# dualHbridge-v5.net
KiCad netlist of a schematic drawn in EAGLE
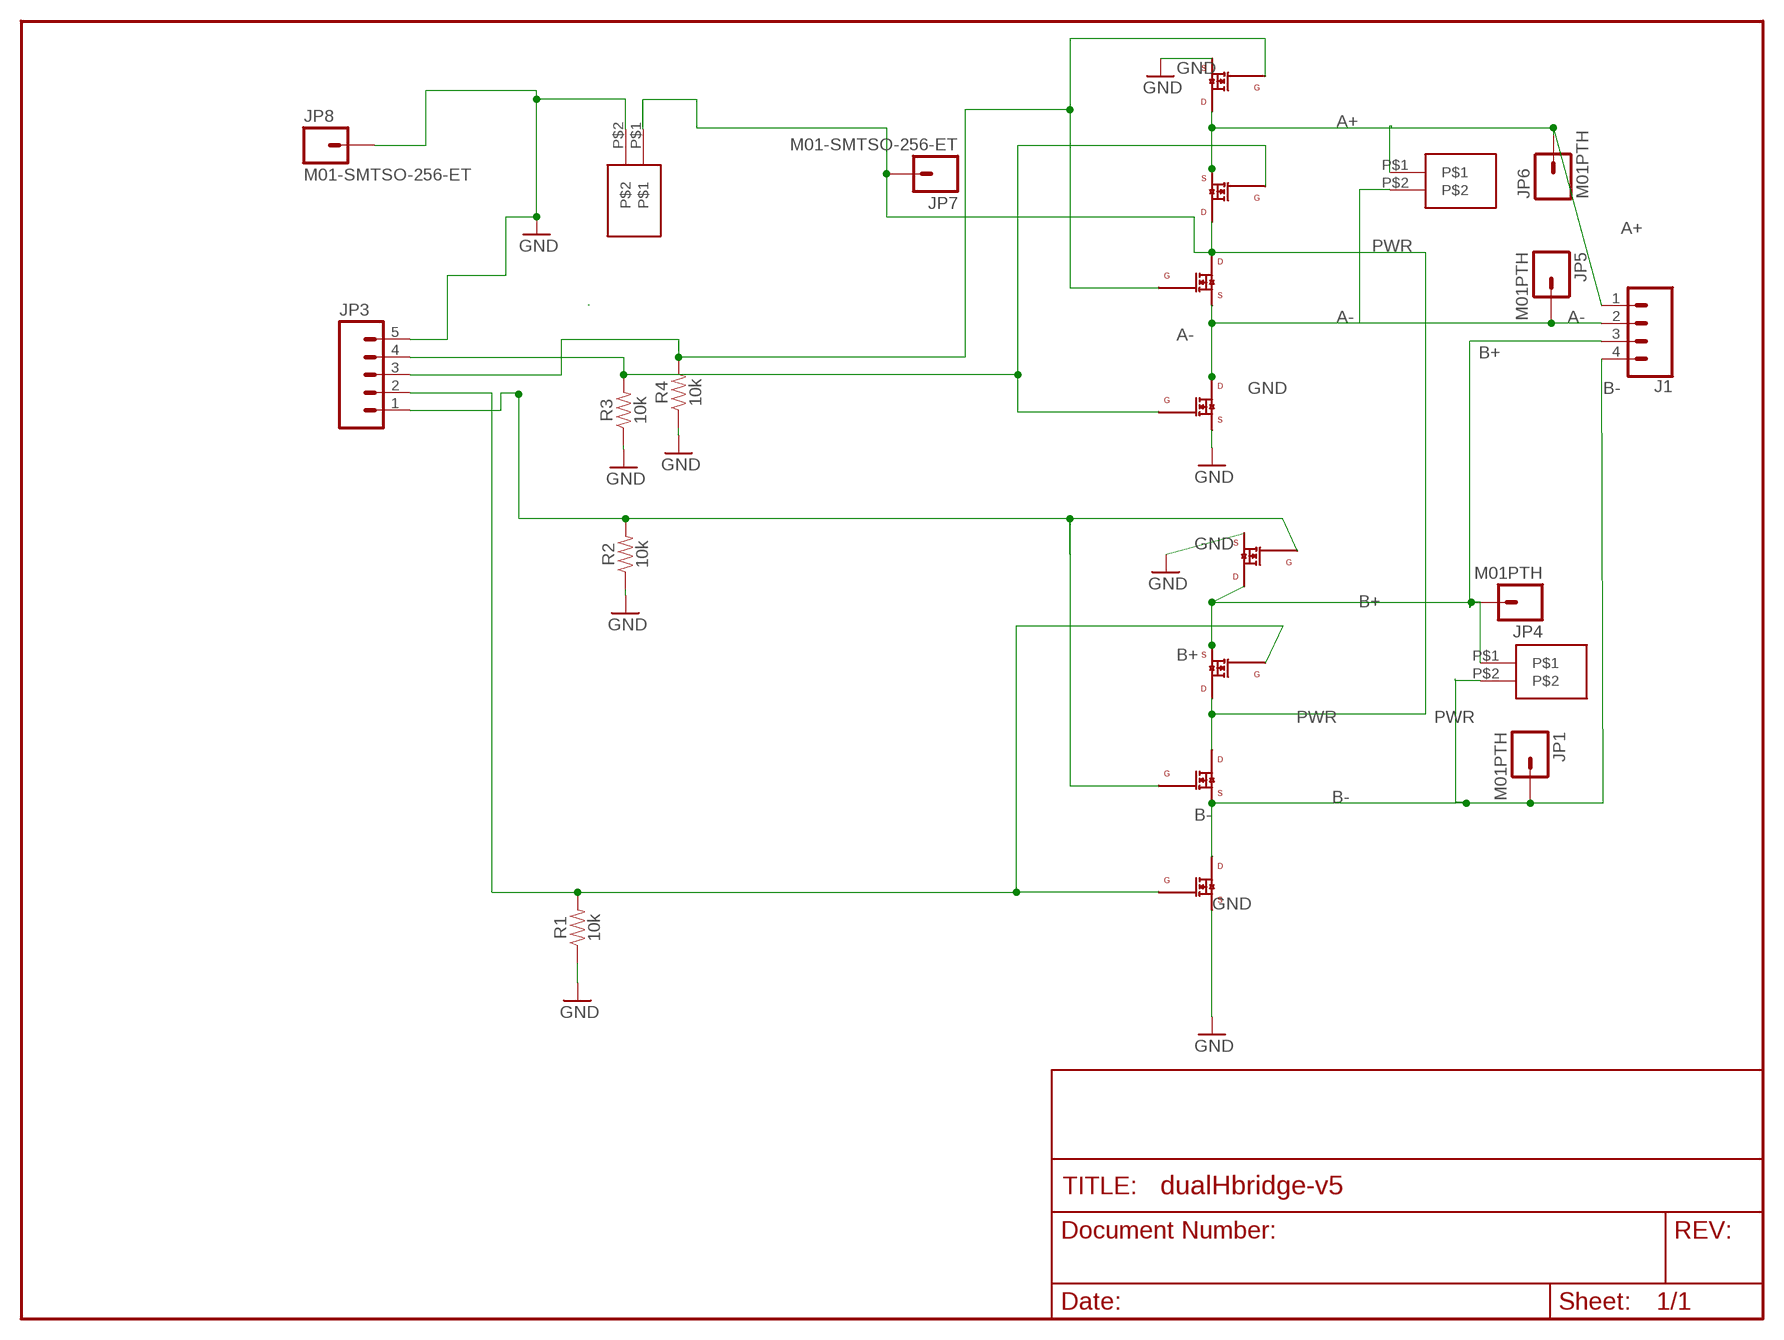
[diagram p0: schematic, sheet 1]

(export (version "E")
  (design (tool "Eeschema 10.0.6"))
  (components
    (comp (ref "J1")
      (value "CONN_04")
      (footprint "eagle-import:1X04")
      (libsource (lib "eagle-import") (part "CONN_04"))
    )
    (comp (ref "JP1")
      (value "M01PTH")
      (footprint "eagle-import:1X01@1")
      (libsource (lib "eagle-import") (part "M01PTH"))
    )
    (comp (ref "JP3")
      (value "M05PTH")
      (footprint "eagle-import:1X05")
      (libsource (lib "eagle-import") (part "M05PTH"))
    )
    (comp (ref "JP4")
      (value "M01PTH")
      (footprint "eagle-import:1X01@1")
      (libsource (lib "eagle-import") (part "M01PTH"))
    )
    (comp (ref "JP5")
      (value "M01PTH")
      (footprint "eagle-import:1X01@1")
      (libsource (lib "eagle-import") (part "M01PTH"))
    )
    (comp (ref "JP6")
      (value "M01PTH")
      (footprint "eagle-import:1X01@1")
      (libsource (lib "eagle-import") (part "M01PTH"))
    )
    (comp (ref "JP7")
      (value "M01-SMTSO-256-ET")
      (footprint "eagle-import:SMTSO-256-ET")
      (libsource (lib "eagle-import") (part "M01-SMTSO-256-ET"))
    )
    (comp (ref "JP8")
      (value "M01-SMTSO-256-ET")
      (footprint "eagle-import:SMTSO-256-ET")
      (libsource (lib "eagle-import") (part "M01-SMTSO-256-ET"))
    )
    (comp (ref "Q1")
      (value "IRLML0060")
      (footprint "eagle-import:SOT-23")
      (libsource (lib "eagle-import") (part "IRLML0060"))
    )
    (comp (ref "Q2")
      (value "IRLML0060")
      (footprint "eagle-import:SOT-23")
      (libsource (lib "eagle-import") (part "IRLML0060"))
    )
    (comp (ref "Q3")
      (value "IRLML0060")
      (footprint "eagle-import:SOT-23")
      (libsource (lib "eagle-import") (part "IRLML0060"))
    )
    (comp (ref "Q4")
      (value "IRLML0060")
      (footprint "eagle-import:SOT-23")
      (libsource (lib "eagle-import") (part "IRLML0060"))
    )
    (comp (ref "Q5")
      (value "IRLML0060")
      (footprint "eagle-import:SOT-23")
      (libsource (lib "eagle-import") (part "IRLML0060"))
    )
    (comp (ref "Q6")
      (value "IRLML0060")
      (footprint "eagle-import:SOT-23")
      (libsource (lib "eagle-import") (part "IRLML0060"))
    )
    (comp (ref "Q7")
      (value "IRLML0060")
      (footprint "eagle-import:SOT-23")
      (libsource (lib "eagle-import") (part "IRLML0060"))
    )
    (comp (ref "Q8")
      (value "IRLML0060")
      (footprint "eagle-import:SOT-23")
      (libsource (lib "eagle-import") (part "IRLML0060"))
    )
    (comp (ref "R1")
      (value "10k")
      (footprint "eagle-import:0603")
      (libsource (lib "eagle-import") (part "10KOHM-0603-1/10W-1%"))
    )
    (comp (ref "R2")
      (value "10k")
      (footprint "eagle-import:0603")
      (libsource (lib "eagle-import") (part "10KOHM-0603-1/10W-1%"))
    )
    (comp (ref "R3")
      (value "10k")
      (footprint "eagle-import:0603")
      (libsource (lib "eagle-import") (part "10KOHM-0603-1/10W-1%"))
    )
    (comp (ref "R4")
      (value "10k")
      (footprint "eagle-import:0603")
      (libsource (lib "eagle-import") (part "10KOHM-0603-1/10W-1%"))
    )
    (comp (ref "X1")
      (value "SPRING-TERMINAL")
      (footprint "eagle-import:SPRING-TERMINAL")
      (libsource (lib "eagle-import") (part "SPRING-TERMINAL"))
    )
    (comp (ref "X2")
      (value "SPRING-TERMINAL")
      (footprint "eagle-import:SPRING-TERMINAL")
      (libsource (lib "eagle-import") (part "SPRING-TERMINAL"))
    )
    (comp (ref "X3")
      (value "SPRING-TERMINAL")
      (footprint "eagle-import:SPRING-TERMINAL")
      (libsource (lib "eagle-import") (part "SPRING-TERMINAL"))
    )
  )
  (nets
    (net (code "1") (name "/A+") (class "Default")
      (node (ref "J1") (pin "1") (pinfunction "1_1") (pintype "passive"))
      (node (ref "JP6") (pin "1") (pinfunction "1_1") (pintype "passive"))
      (node (ref "Q1") (pin "3") (pinfunction "DRAIN_3") (pintype "bidirectional"))
      (node (ref "Q2") (pin "2") (pinfunction "SOURCE_2") (pintype "bidirectional"))
      (node (ref "X1") (pin "P$1") (pinfunction "P$1_P$1") (pintype "bidirectional"))
    )
    (net (code "2") (name "/A-") (class "Default")
      (node (ref "J1") (pin "2") (pinfunction "2_2") (pintype "passive"))
      (node (ref "JP5") (pin "1") (pinfunction "1_1") (pintype "passive"))
      (node (ref "Q3") (pin "2") (pinfunction "SOURCE_2") (pintype "bidirectional"))
      (node (ref "Q4") (pin "3") (pinfunction "DRAIN_3") (pintype "bidirectional"))
      (node (ref "X1") (pin "P$2") (pinfunction "P$2_P$2") (pintype "bidirectional"))
    )
    (net (code "3") (name "/B+") (class "Default")
      (node (ref "J1") (pin "3") (pinfunction "3_3") (pintype "passive"))
      (node (ref "JP4") (pin "1") (pinfunction "1_1") (pintype "passive"))
      (node (ref "Q5") (pin "3") (pinfunction "DRAIN_3") (pintype "bidirectional"))
      (node (ref "Q6") (pin "2") (pinfunction "SOURCE_2") (pintype "bidirectional"))
      (node (ref "X2") (pin "P$1") (pinfunction "P$1_P$1") (pintype "bidirectional"))
    )
    (net (code "4") (name "/B-") (class "Default")
      (node (ref "J1") (pin "4") (pinfunction "4_4") (pintype "passive"))
      (node (ref "JP1") (pin "1") (pinfunction "1_1") (pintype "passive"))
      (node (ref "Q7") (pin "2") (pinfunction "SOURCE_2") (pintype "bidirectional"))
      (node (ref "Q8") (pin "3") (pinfunction "DRAIN_3") (pintype "bidirectional"))
      (node (ref "X2") (pin "P$2") (pinfunction "P$2_P$2") (pintype "bidirectional"))
    )
    (net (code "5") (name "/PWR") (class "Default")
      (node (ref "JP7") (pin "P$1") (pinfunction "1_P$1") (pintype "passive"))
      (node (ref "Q2") (pin "3") (pinfunction "DRAIN_3") (pintype "bidirectional"))
      (node (ref "Q3") (pin "3") (pinfunction "DRAIN_3") (pintype "bidirectional"))
      (node (ref "Q6") (pin "3") (pinfunction "DRAIN_3") (pintype "bidirectional"))
      (node (ref "Q7") (pin "3") (pinfunction "DRAIN_3") (pintype "bidirectional"))
      (node (ref "X3") (pin "P$1") (pinfunction "P$1_P$1") (pintype "bidirectional"))
    )
    (net (code "6") (name "GND") (class "Default")
      (node (ref "JP3") (pin "5") (pinfunction "5_5") (pintype "passive"))
      (node (ref "JP8") (pin "P$1") (pinfunction "1_P$1") (pintype "passive"))
      (node (ref "Q1") (pin "2") (pinfunction "SOURCE_2") (pintype "bidirectional"))
      (node (ref "Q4") (pin "2") (pinfunction "SOURCE_2") (pintype "bidirectional"))
      (node (ref "Q5") (pin "2") (pinfunction "SOURCE_2") (pintype "bidirectional"))
      (node (ref "Q8") (pin "2") (pinfunction "SOURCE_2") (pintype "bidirectional"))
      (node (ref "R1") (pin "1") (pinfunction "1_1") (pintype "passive"))
      (node (ref "R2") (pin "1") (pinfunction "1_1") (pintype "passive"))
      (node (ref "R3") (pin "1") (pinfunction "1_1") (pintype "passive"))
      (node (ref "R4") (pin "1") (pinfunction "1_1") (pintype "passive"))
      (node (ref "X3") (pin "P$2") (pinfunction "P$2_P$2") (pintype "bidirectional"))
    )
    (net (code "7") (name "Net-(Q1-GATE)") (class "Default")
      (node (ref "JP3") (pin "3") (pinfunction "3_3") (pintype "passive"))
      (node (ref "Q1") (pin "1") (pinfunction "GATE_1") (pintype "bidirectional"))
      (node (ref "Q3") (pin "1") (pinfunction "GATE_1") (pintype "bidirectional"))
      (node (ref "R4") (pin "2") (pinfunction "2_2") (pintype "passive"))
    )
    (net (code "8") (name "Net-(Q2-GATE)") (class "Default")
      (node (ref "JP3") (pin "4") (pinfunction "4_4") (pintype "passive"))
      (node (ref "Q2") (pin "1") (pinfunction "GATE_1") (pintype "bidirectional"))
      (node (ref "Q4") (pin "1") (pinfunction "GATE_1") (pintype "bidirectional"))
      (node (ref "R3") (pin "2") (pinfunction "2_2") (pintype "passive"))
    )
    (net (code "9") (name "Net-(Q5-GATE)") (class "Default")
      (node (ref "JP3") (pin "1") (pinfunction "1_1") (pintype "passive"))
      (node (ref "Q5") (pin "1") (pinfunction "GATE_1") (pintype "bidirectional"))
      (node (ref "Q7") (pin "1") (pinfunction "GATE_1") (pintype "bidirectional"))
      (node (ref "R2") (pin "2") (pinfunction "2_2") (pintype "passive"))
    )
    (net (code "10") (name "Net-(Q6-GATE)") (class "Default")
      (node (ref "JP3") (pin "2") (pinfunction "2_2") (pintype "passive"))
      (node (ref "Q6") (pin "1") (pinfunction "GATE_1") (pintype "bidirectional"))
      (node (ref "Q8") (pin "1") (pinfunction "GATE_1") (pintype "bidirectional"))
      (node (ref "R1") (pin "2") (pinfunction "2_2") (pintype "passive"))
    )
  )
)
